# FLASH.net
KiCad netlist of a schematic drawn in EasyEDA Pro
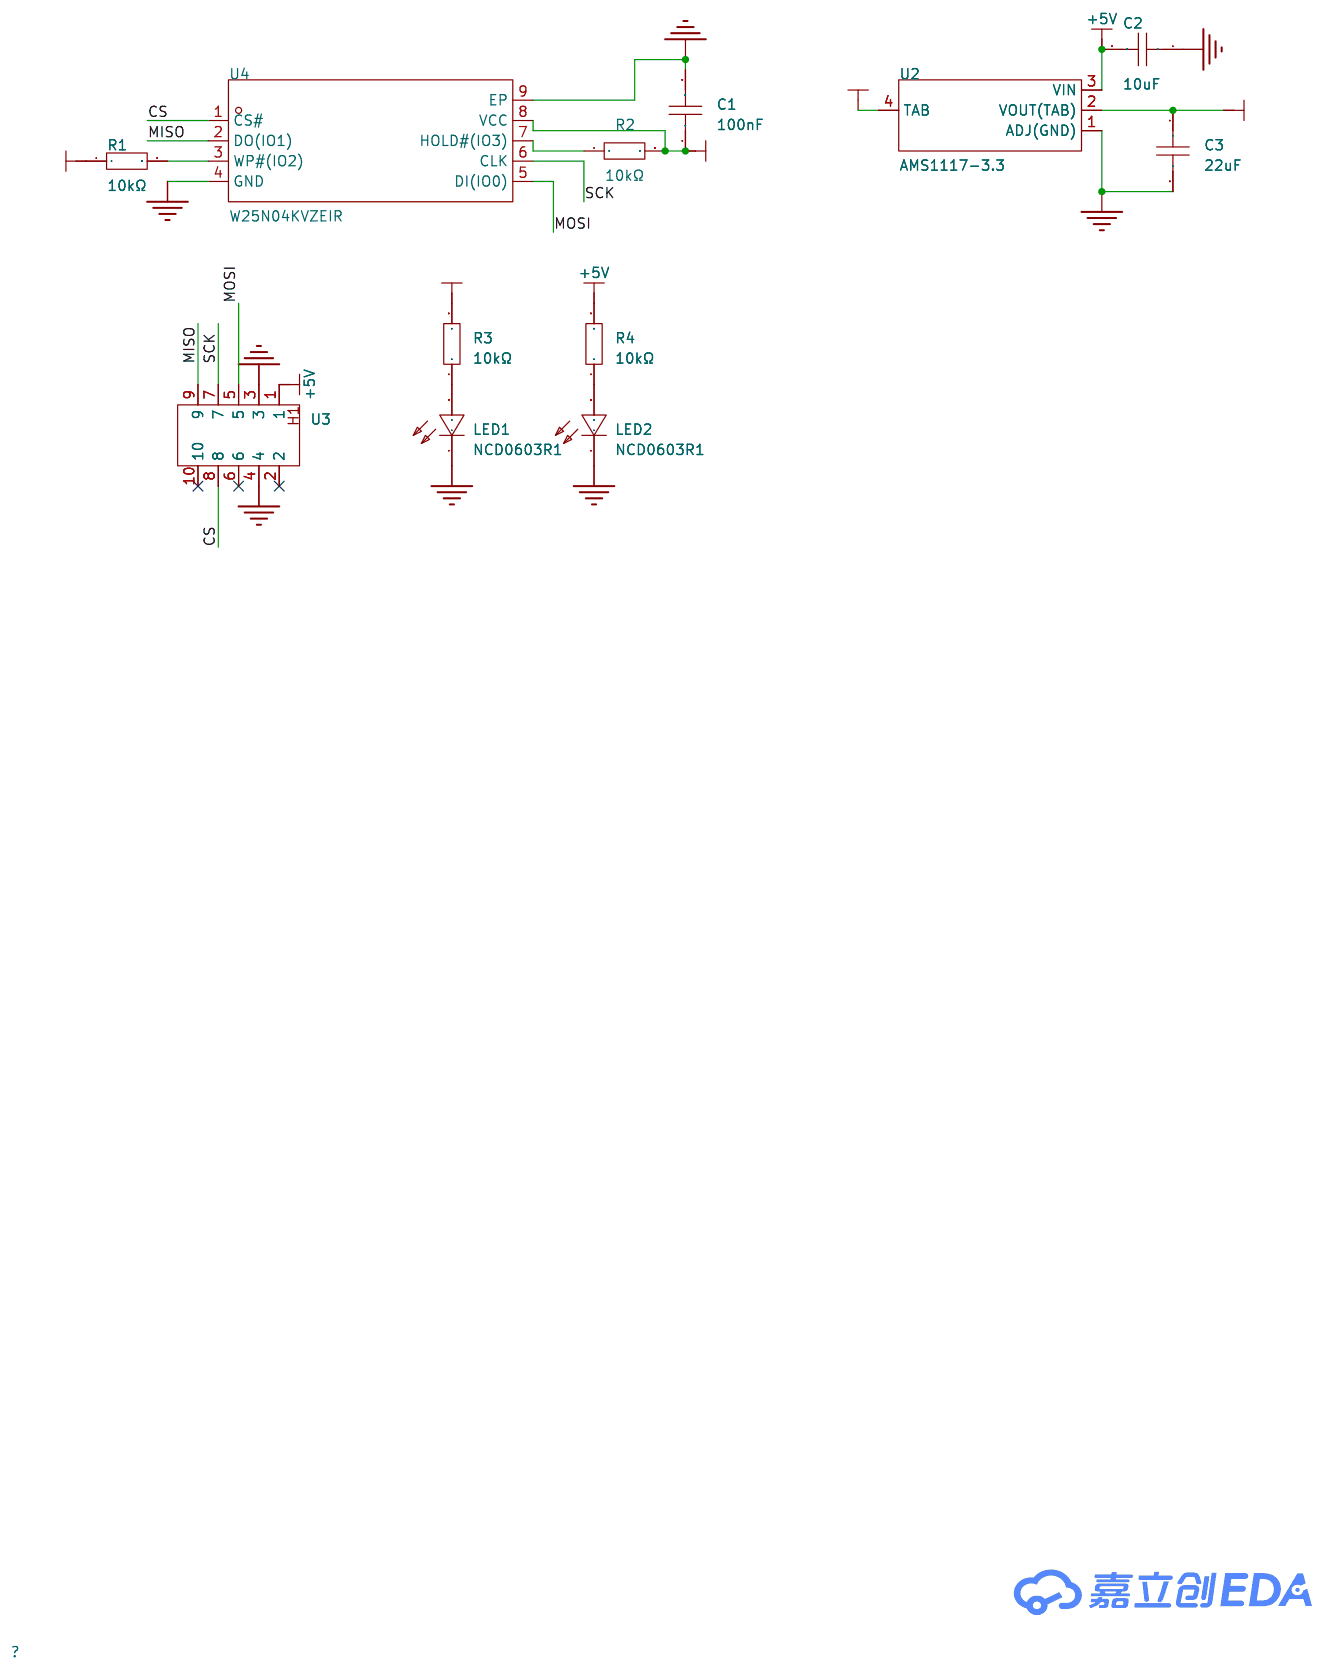
[diagram p0: schematic sheet]

(export (version "E")
  (design (tool "Eeschema 10.0.6"))
  (components
    (comp (ref "C1")
      (value "100nF")
      (footprint "easyedapro:C0603")
      (description "容值:100nF;精度:±10%;额定电压:50V;温度系数:X7R;")
      (fields
        (field (name "Manufacturer Part") "CGA0603X7R104K500JT")
        (field (name "Manufacturer") "HRE(芯声)")
      )
      (libsource (lib "easyedapro") (part "CGA0603X7R104K500JT"))
    )
    (comp (ref "C2")
      (value "10uF")
      (footprint "easyedapro:C0603")
      (description "容值:10uF;精度:±10%;额定电压:10V;温度系数:X5R;")
      (fields
        (field (name "Manufacturer Part") "CGA0603X5R106K100JT")
        (field (name "Manufacturer") "HRE(芯声)")
      )
      (libsource (lib "easyedapro") (part "CGA0603X5R106K100JT"))
    )
    (comp (ref "C3")
      (value "22uF")
      (footprint "easyedapro:C0603")
      (description "容值:22uF;精度:±20%;额定电压:16V;温度系数:X5R;")
      (fields
        (field (name "Manufacturer Part") "CGA0603X5R226M160JT")
        (field (name "Manufacturer") "HRE(芯声)")
      )
      (libsource (lib "easyedapro") (part "CGA0603X5R226M160JT"))
    )
    (comp (ref "LED1")
      (value "NCD0603R1")
      (footprint "easyedapro:LED0603-RD_RED")
      (fields (field (name "Manufacturer") "国星光电"))
      (libsource (lib "easyedapro") (part "FC-DA1608HRK-620D"))
    )
    (comp (ref "LED2")
      (value "NCD0603R1")
      (footprint "easyedapro:LED0603-RD_RED")
      (fields (field (name "Manufacturer") "国星光电"))
      (libsource (lib "easyedapro") (part "FC-DA1608HRK-620D"))
    )
    (comp (ref "R1")
      (value "10kΩ")
      (footprint "easyedapro:R0603")
      (description "电阻类型:厚膜电阻;阻值:10kΩ;精度:±1%;功率:100mW;最大工作电压:75V;温度系数:±100ppm/°C;")
      (fields
        (field (name "Manufacturer Part") "0603WAF1002T5E")
        (field (name "Manufacturer") "UNI-ROYAL(厚声)")
      )
      (libsource (lib "easyedapro") (part "0603WAF1002T5E"))
    )
    (comp (ref "R2")
      (value "10kΩ")
      (footprint "easyedapro:R0603")
      (description "电阻类型:厚膜电阻;阻值:10kΩ;精度:±1%;功率:100mW;最大工作电压:75V;温度系数:±100ppm/°C;")
      (fields
        (field (name "Manufacturer Part") "0603WAF1002T5E")
        (field (name "Manufacturer") "UNI-ROYAL(厚声)")
      )
      (libsource (lib "easyedapro") (part "0603WAF1002T5E"))
    )
    (comp (ref "R3")
      (value "10kΩ")
      (footprint "easyedapro:R0603")
      (description "电阻类型:厚膜电阻;阻值:10kΩ;精度:±1%;功率:100mW;最大工作电压:75V;温度系数:±100ppm/°C;")
      (fields
        (field (name "Manufacturer Part") "0603WAF1002T5E")
        (field (name "Manufacturer") "UNI-ROYAL(厚声)")
      )
      (libsource (lib "easyedapro") (part "0603WAF1002T5E"))
    )
    (comp (ref "R4")
      (value "10kΩ")
      (footprint "easyedapro:R0603")
      (description "电阻类型:厚膜电阻;阻值:10kΩ;精度:±1%;功率:100mW;最大工作电压:75V;温度系数:±100ppm/°C;")
      (fields
        (field (name "Manufacturer Part") "0603WAF1002T5E")
        (field (name "Manufacturer") "UNI-ROYAL(厚声)")
      )
      (libsource (lib "easyedapro") (part "0603WAF1002T5E"))
    )
    (comp (ref "U2")
      (value "AMS1117-3.3")
      (footprint "easyedapro:SOT-223-4_L6.5-W3.5-P2.30-LS7.0-BR")
      (description "输出类型:固定;工作电压:12V;输出电压:3.3V;输出电流:1A;电源纹波抑制比(PSRR):60dB@(120Hz);输出极性:正极;")
      (fields (field (name "Manufacturer") "UMW(友台半导体)"))
      (libsource (lib "easyedapro") (part "AMS1117-3.3_C347222"))
    )
    (comp (ref "U3")
      (value "~")
      (footprint "easyedapro:2_5 双面 排针")
      (libsource (lib "easyedapro") (part "2*5 双面"))
    )
    (comp (ref "U4")
      (value "W25N04KVZEIR")
      (footprint "easyedapro:WSON-8_L8.0-W6.0-P1.27-TL-1")
      (description "存储容量:4Gbit;时钟频率(fc):104MHz;工作电压:2.7V~3.6V;")
      (fields (field (name "Manufacturer") "WINBOND(华邦)"))
      (libsource (lib "easyedapro") (part "W25N04KVZEIR"))
    )
  )
  (nets
    (net (code "1") (name "+5V") (class "Default")
      (node (ref "C2") (pin "2") (pinfunction "2_2") (pintype "unspecified"))
      (node (ref "R4") (pin "2") (pinfunction "2_2") (pintype "input"))
      (node (ref "U2") (pin "3") (pinfunction "VIN_3") (pintype "unspecified"))
      (node (ref "U3") (pin "1") (pinfunction "1_1") (pintype "unspecified"))
    )
    (net (code "2") (name "/CS") (class "Default")
      (node (ref "U3") (pin "8") (pinfunction "8_8") (pintype "unspecified"))
      (node (ref "U4") (pin "1") (pinfunction "CS#_1") (pintype "unspecified"))
    )
    (net (code "3") (name "/MISO") (class "Default")
      (node (ref "U3") (pin "9") (pinfunction "9_9") (pintype "unspecified"))
      (node (ref "U4") (pin "2") (pinfunction "DO(IO1)_2") (pintype "unspecified"))
    )
    (net (code "4") (name "/MOSI") (class "Default")
      (node (ref "U3") (pin "5") (pinfunction "5_5") (pintype "unspecified"))
      (node (ref "U4") (pin "5") (pinfunction "DI(IO0)_5") (pintype "unspecified"))
    )
    (net (code "5") (name "/SCK") (class "Default")
      (node (ref "U3") (pin "7") (pinfunction "7_7") (pintype "unspecified"))
      (node (ref "U4") (pin "6") (pinfunction "CLK_6") (pintype "unspecified"))
    )
    (net (code "6") (name "GND") (class "Default")
      (node (ref "C1") (pin "2") (pinfunction "2_2") (pintype "unspecified"))
      (node (ref "C2") (pin "1") (pinfunction "1_1") (pintype "unspecified"))
      (node (ref "C3") (pin "2") (pinfunction "2_2") (pintype "unspecified"))
      (node (ref "LED1") (pin "1") (pinfunction "K_1") (pintype "input"))
      (node (ref "LED2") (pin "1") (pinfunction "K_1") (pintype "input"))
      (node (ref "U2") (pin "1") (pinfunction "ADJ(GND)_1") (pintype "unspecified"))
      (node (ref "U3") (pin "3") (pinfunction "3_3") (pintype "unspecified"))
      (node (ref "U3") (pin "4") (pinfunction "4_4") (pintype "unspecified"))
      (node (ref "U4") (pin "4") (pinfunction "GND_4") (pintype "unspecified"))
      (node (ref "U4") (pin "9") (pinfunction "EP_9") (pintype "unspecified"))
    )
    (net (code "7") (name "Net-(LED1-A)") (class "Default")
      (node (ref "LED1") (pin "2") (pinfunction "A_2") (pintype "input"))
      (node (ref "R3") (pin "1") (pinfunction "1_1") (pintype "input"))
    )
    (net (code "8") (name "Net-(LED2-A)") (class "Default")
      (node (ref "LED2") (pin "2") (pinfunction "A_2") (pintype "input"))
      (node (ref "R4") (pin "1") (pinfunction "1_1") (pintype "input"))
    )
    (net (code "9") (name "Net-(U4-HOLD#(IO3))") (class "Default")
      (node (ref "R2") (pin "1") (pinfunction "1_1") (pintype "input"))
      (node (ref "U4") (pin "7") (pinfunction "HOLD#(IO3)_7") (pintype "unspecified"))
    )
    (net (code "10") (name "Net-(U4-WP#(IO2))") (class "Default")
      (node (ref "R1") (pin "2") (pinfunction "2_2") (pintype "input"))
      (node (ref "U4") (pin "3") (pinfunction "WP#(IO2)_3") (pintype "unspecified"))
    )
    (net (code "11") (name "VCC-3.3") (class "Default")
      (node (ref "C1") (pin "1") (pinfunction "1_1") (pintype "unspecified"))
      (node (ref "C3") (pin "1") (pinfunction "1_1") (pintype "unspecified"))
      (node (ref "R1") (pin "1") (pinfunction "1_1") (pintype "input"))
      (node (ref "R2") (pin "2") (pinfunction "2_2") (pintype "input"))
      (node (ref "R3") (pin "2") (pinfunction "2_2") (pintype "input"))
      (node (ref "U2") (pin "2") (pinfunction "VOUT(TAB)_2") (pintype "unspecified"))
      (node (ref "U2") (pin "4") (pinfunction "TAB_4") (pintype "unspecified"))
      (node (ref "U4") (pin "8") (pinfunction "VCC_8") (pintype "unspecified"))
    )
    (net (code "12") (name "unconnected-(U3-Pad2)") (class "Default")
      (node (ref "U3") (pin "2") (pinfunction "2_2") (pintype "unspecified+no_connect"))
    )
    (net (code "13") (name "unconnected-(U3-Pad6)") (class "Default")
      (node (ref "U3") (pin "6") (pinfunction "6_6") (pintype "unspecified+no_connect"))
    )
    (net (code "14") (name "unconnected-(U3-Pad10)") (class "Default")
      (node (ref "U3") (pin "10") (pinfunction "10_10") (pintype "unspecified+no_connect"))
    )
  )
)
